# Power_Stage.net
KiCad netlist of a schematic drawn in Altium Designer
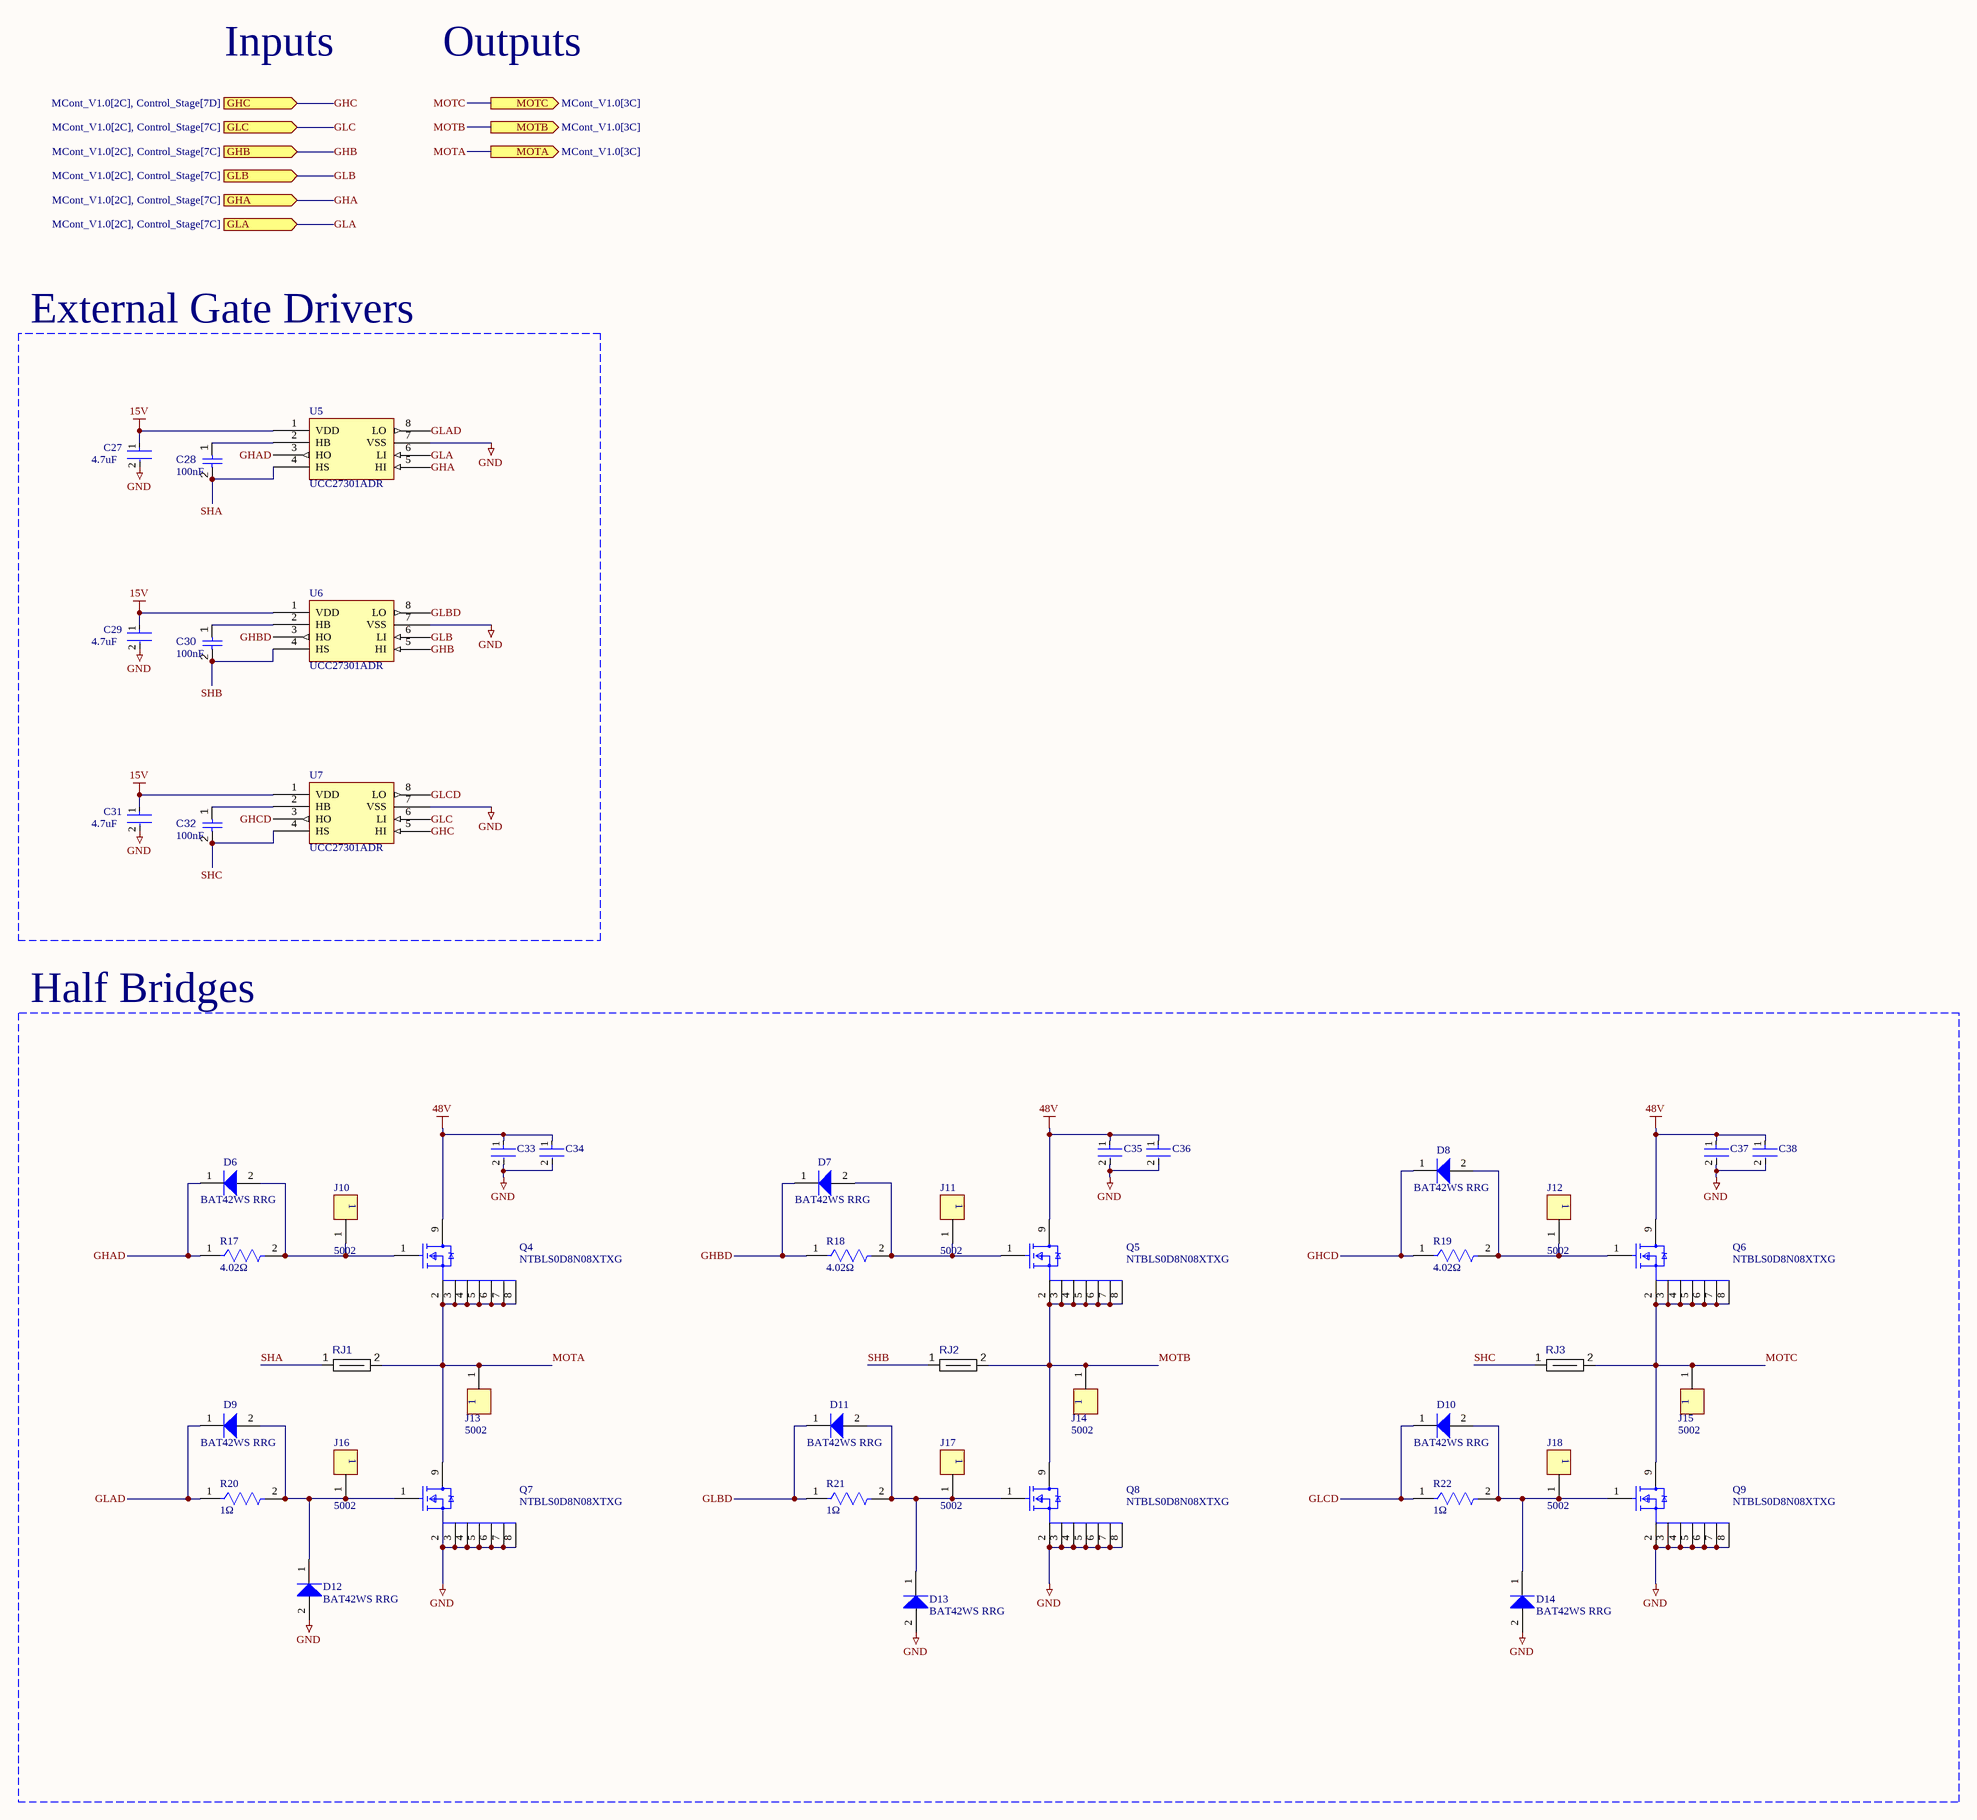
[diagram p0: Power_Stage.SchDoc]

(export (version "E")
  (design (tool "Eeschema 10.0.6"))
  (components
    (comp (ref "C27")
      (value "CL21A475KAQNNNE")
      (footprint "FP-CL21-IPC_A")
      (description "CL21 Series 0805 4.7uF 25V ±10% Tolerance X5R Multilayer Ceramic Chip Capacitor")
      (fields (field (name "CAPACITANCE") "4.7uF") (field (name "TOLERANCE") "10%"))
      (libsource (lib "Altium Content Vault") (part "b4654b650e69147ec39a6b967a45e02"))
    )
    (comp (ref "C28")
      (value "100nF")
      (footprint "FP-CL10-IPC_B")
      (fields (field (name "Comment") "CL10B104KC8NNNC"))
      (libsource (lib "CEV Electrical") (part "CAP-NP-2"))
    )
    (comp (ref "C29")
      (value "CL21A475KAQNNNE")
      (footprint "FP-CL21-IPC_A")
      (description "CL21 Series 0805 4.7uF 25V ±10% Tolerance X5R Multilayer Ceramic Chip Capacitor")
      (fields (field (name "CAPACITANCE") "4.7uF") (field (name "TOLERANCE") "10%"))
      (libsource (lib "Altium Content Vault") (part "b4654b650e69147ec39a6b967a45e02"))
    )
    (comp (ref "C30")
      (value "100nF")
      (footprint "FP-CL10-IPC_B")
      (fields (field (name "Comment") "CL10B104KC8NNNC"))
      (libsource (lib "CEV Electrical") (part "CAP-NP-2"))
    )
    (comp (ref "C31")
      (value "CL21A475KAQNNNE")
      (footprint "FP-CL21-IPC_A")
      (description "CL21 Series 0805 4.7uF 25V ±10% Tolerance X5R Multilayer Ceramic Chip Capacitor")
      (fields (field (name "CAPACITANCE") "4.7uF") (field (name "TOLERANCE") "10%"))
      (libsource (lib "Altium Content Vault") (part "b4654b650e69147ec39a6b967a45e02"))
    )
    (comp (ref "C32")
      (value "100nF")
      (footprint "FP-CL10-IPC_B")
      (fields (field (name "Comment") "CL10B104KC8NNNC"))
      (libsource (lib "CEV Electrical") (part "CAP-NP-2"))
    )
    (comp (ref "C33")
      (value "C1210C105K1RACTU")
      (footprint "FP-C1210C105K1RACTU-MFG")
      (description "CAP CER 1UF 100V X7R 1210")
      (fields (field (name "VOLTAGE") "100V") (field (name "TOLERANCE") "10%"))
      (libsource (lib "Altium Content Vault") (part "b4654b650e69147ec39a6b967a45e02"))
    )
    (comp (ref "C34")
      (value "C1210C105K1RACTU")
      (footprint "FP-C1210C105K1RACTU-MFG")
      (description "CAP CER 1UF 100V X7R 1210")
      (fields (field (name "VOLTAGE") "100V") (field (name "TOLERANCE") "10%"))
      (libsource (lib "Altium Content Vault") (part "b4654b650e69147ec39a6b967a45e02"))
    )
    (comp (ref "C35")
      (value "C1210C105K1RACTU")
      (footprint "FP-C1210C105K1RACTU-MFG")
      (description "CAP CER 1UF 100V X7R 1210")
      (fields (field (name "VOLTAGE") "100V") (field (name "TOLERANCE") "10%"))
      (libsource (lib "Altium Content Vault") (part "b4654b650e69147ec39a6b967a45e02"))
    )
    (comp (ref "C36")
      (value "C1210C105K1RACTU")
      (footprint "FP-C1210C105K1RACTU-MFG")
      (description "CAP CER 1UF 100V X7R 1210")
      (fields (field (name "VOLTAGE") "100V") (field (name "TOLERANCE") "10%"))
      (libsource (lib "Altium Content Vault") (part "b4654b650e69147ec39a6b967a45e02"))
    )
    (comp (ref "C37")
      (value "C1210C105K1RACTU")
      (footprint "FP-C1210C105K1RACTU-MFG")
      (description "CAP CER 1UF 100V X7R 1210")
      (fields (field (name "VOLTAGE") "100V") (field (name "TOLERANCE") "10%"))
      (libsource (lib "Altium Content Vault") (part "b4654b650e69147ec39a6b967a45e02"))
    )
    (comp (ref "C38")
      (value "C1210C105K1RACTU")
      (footprint "FP-C1210C105K1RACTU-MFG")
      (description "CAP CER 1UF 100V X7R 1210")
      (fields (field (name "VOLTAGE") "100V") (field (name "TOLERANCE") "10%"))
      (libsource (lib "Altium Content Vault") (part "b4654b650e69147ec39a6b967a45e02"))
    )
    (comp (ref "D6")
      (value "BAT42WS RRG")
      (footprint "BAT42WS RRG-Footprint-1")
      (description "Schottky Diode, 30V, 0.2A, Sod-323F Rohs Compliant: Yes")
      (libsource (lib "CEV Electrical New") (part "BAT42WS RRG-Symbol-1"))
    )
    (comp (ref "D7")
      (value "BAT42WS RRG")
      (footprint "BAT42WS RRG-Footprint-1")
      (description "Schottky Diode, 30V, 0.2A, Sod-323F Rohs Compliant: Yes")
      (libsource (lib "CEV Electrical New") (part "BAT42WS RRG-Symbol-1"))
    )
    (comp (ref "D8")
      (value "BAT42WS RRG")
      (footprint "BAT42WS RRG-Footprint-1")
      (description "Schottky Diode, 30V, 0.2A, Sod-323F Rohs Compliant: Yes")
      (libsource (lib "CEV Electrical New") (part "BAT42WS RRG-Symbol-1"))
    )
    (comp (ref "D9")
      (value "BAT42WS RRG")
      (footprint "BAT42WS RRG-Footprint-1")
      (description "Schottky Diode, 30V, 0.2A, Sod-323F Rohs Compliant: Yes")
      (libsource (lib "CEV Electrical New") (part "BAT42WS RRG-Symbol-1"))
    )
    (comp (ref "D10")
      (value "BAT42WS RRG")
      (footprint "BAT42WS RRG-Footprint-1")
      (description "Schottky Diode, 30V, 0.2A, Sod-323F Rohs Compliant: Yes")
      (libsource (lib "CEV Electrical New") (part "BAT42WS RRG-Symbol-1"))
    )
    (comp (ref "D11")
      (value "BAT42WS RRG")
      (footprint "BAT42WS RRG-Footprint-1")
      (description "Schottky Diode, 30V, 0.2A, Sod-323F Rohs Compliant: Yes")
      (libsource (lib "CEV Electrical New") (part "BAT42WS RRG-Symbol-1"))
    )
    (comp (ref "D12")
      (value "BAT42WS RRG")
      (footprint "BAT42WS RRG-Footprint-1")
      (description "Schottky Diode, 30V, 0.2A, Sod-323F Rohs Compliant: Yes")
      (libsource (lib "CEV Electrical New") (part "BAT42WS RRG-Symbol-1"))
    )
    (comp (ref "D13")
      (value "BAT42WS RRG")
      (footprint "BAT42WS RRG-Footprint-1")
      (description "Schottky Diode, 30V, 0.2A, Sod-323F Rohs Compliant: Yes")
      (libsource (lib "CEV Electrical New") (part "BAT42WS RRG-Symbol-1"))
    )
    (comp (ref "D14")
      (value "BAT42WS RRG")
      (footprint "BAT42WS RRG-Footprint-1")
      (description "Schottky Diode, 30V, 0.2A, Sod-323F Rohs Compliant: Yes")
      (libsource (lib "CEV Electrical New") (part "BAT42WS RRG-Symbol-1"))
    )
    (comp (ref "J10")
      (value "5002")
      (footprint "FP-5002-MFG")
      (description "PC TEST POINT MINIATURE WHITE")
      (libsource (lib "Altium Content Vault") (part "1e4615820a309e3ce90f9e6d957b7fa"))
    )
    (comp (ref "J11")
      (value "5002")
      (footprint "FP-5002-MFG")
      (description "PC TEST POINT MINIATURE WHITE")
      (libsource (lib "Altium Content Vault") (part "1e4615820a309e3ce90f9e6d957b7fa"))
    )
    (comp (ref "J12")
      (value "5002")
      (footprint "FP-5002-MFG")
      (description "PC TEST POINT MINIATURE WHITE")
      (libsource (lib "Altium Content Vault") (part "1e4615820a309e3ce90f9e6d957b7fa"))
    )
    (comp (ref "J13")
      (value "5002")
      (footprint "FP-5002-MFG")
      (description "PC TEST POINT MINIATURE WHITE")
      (libsource (lib "") (part "1e4615820a309e3ce90f9e6d957b7fa_1"))
    )
    (comp (ref "J14")
      (value "5002")
      (footprint "FP-5002-MFG")
      (description "PC TEST POINT MINIATURE WHITE")
      (libsource (lib "") (part "1e4615820a309e3ce90f9e6d957b7fa_1"))
    )
    (comp (ref "J15")
      (value "5002")
      (footprint "FP-5002-MFG")
      (description "PC TEST POINT MINIATURE WHITE")
      (libsource (lib "") (part "1e4615820a309e3ce90f9e6d957b7fa_1"))
    )
    (comp (ref "J16")
      (value "5002")
      (footprint "FP-5002-MFG")
      (description "PC TEST POINT MINIATURE WHITE")
      (libsource (lib "Altium Content Vault") (part "1e4615820a309e3ce90f9e6d957b7fa"))
    )
    (comp (ref "J17")
      (value "5002")
      (footprint "FP-5002-MFG")
      (description "PC TEST POINT MINIATURE WHITE")
      (libsource (lib "Altium Content Vault") (part "1e4615820a309e3ce90f9e6d957b7fa"))
    )
    (comp (ref "J18")
      (value "5002")
      (footprint "FP-5002-MFG")
      (description "PC TEST POINT MINIATURE WHITE")
      (libsource (lib "Altium Content Vault") (part "1e4615820a309e3ce90f9e6d957b7fa"))
    )
    (comp (ref "Q4")
      (value "NTBLS0D8N08XTXG")
      (footprint "NTBLS0D8N08XTXG")
      (description "NTBL Series N-Channel 457A 325W Surface Mount Power Mosfet HPSOF-8")
      (libsource (lib "CEV Electrical New") (part "NTBLS0D8N08XTXG"))
    )
    (comp (ref "Q5")
      (value "NTBLS0D8N08XTXG")
      (footprint "NTBLS0D8N08XTXG")
      (description "NTBL Series N-Channel 457A 325W Surface Mount Power Mosfet HPSOF-8")
      (libsource (lib "CEV Electrical New") (part "NTBLS0D8N08XTXG"))
    )
    (comp (ref "Q6")
      (value "NTBLS0D8N08XTXG")
      (footprint "NTBLS0D8N08XTXG")
      (description "NTBL Series N-Channel 457A 325W Surface Mount Power Mosfet HPSOF-8")
      (libsource (lib "CEV Electrical New") (part "NTBLS0D8N08XTXG"))
    )
    (comp (ref "Q7")
      (value "NTBLS0D8N08XTXG")
      (footprint "NTBLS0D8N08XTXG")
      (description "NTBL Series N-Channel 457A 325W Surface Mount Power Mosfet HPSOF-8")
      (libsource (lib "CEV Electrical New") (part "NTBLS0D8N08XTXG"))
    )
    (comp (ref "Q8")
      (value "NTBLS0D8N08XTXG")
      (footprint "NTBLS0D8N08XTXG")
      (description "NTBL Series N-Channel 457A 325W Surface Mount Power Mosfet HPSOF-8")
      (libsource (lib "CEV Electrical New") (part "NTBLS0D8N08XTXG"))
    )
    (comp (ref "Q9")
      (value "NTBLS0D8N08XTXG")
      (footprint "NTBLS0D8N08XTXG")
      (description "NTBL Series N-Channel 457A 325W Surface Mount Power Mosfet HPSOF-8")
      (libsource (lib "CEV Electrical New") (part "NTBLS0D8N08XTXG"))
    )
    (comp (ref "R17")
      (value "4.02Ω")
      (footprint "CRCW06034R02FKEAHP-Footprint-1")
      (description "Res Thick Film 0603 4.02 Ohm 1% 0.33W(1/3W) ±100ppm/C Pad SMD Automotive T/R")
      (fields (field (name "TOLERANCE") "1%") (field (name "Comment") "CRCW06034R02FKEAHP"))
      (libsource (lib "CEV Electrical New") (part "CRCW06034R02FKEAHP-Symbol-1"))
    )
    (comp (ref "R18")
      (value "4.02Ω")
      (footprint "CRCW06034R02FKEAHP-Footprint-1")
      (description "Res Thick Film 0603 4.02 Ohm 1% 0.33W(1/3W) ±100ppm/C Pad SMD Automotive T/R")
      (fields (field (name "TOLERANCE") "1%") (field (name "Comment") "CRCW06034R02FKEAHP"))
      (libsource (lib "CEV Electrical New") (part "CRCW06034R02FKEAHP-Symbol-1"))
    )
    (comp (ref "R19")
      (value "4.02Ω")
      (footprint "CRCW06034R02FKEAHP-Footprint-1")
      (description "Res Thick Film 0603 4.02 Ohm 1% 0.33W(1/3W) ±100ppm/C Pad SMD Automotive T/R")
      (fields (field (name "TOLERANCE") "1%") (field (name "Comment") "CRCW06034R02FKEAHP"))
      (libsource (lib "CEV Electrical New") (part "CRCW06034R02FKEAHP-Symbol-1"))
    )
    (comp (ref "R20")
      (value "1Ω")
      (footprint "SR0603FR-7T1RL-Footprint-1")
      (description "Res Thick Film 0603 1 Ohm 1% 0.25W(1/4W) ±200ppm/C Pad SMD Automotive T/R")
      (fields (field (name "TOLERANCE") "1%") (field (name "Comment") "SR0603FR-7T1RL"))
      (libsource (lib "CEV Electrical New") (part "SR0603FR-7T1RL-Symbol-1"))
    )
    (comp (ref "R21")
      (value "1Ω")
      (footprint "SR0603FR-7T1RL-Footprint-1")
      (description "Res Thick Film 0603 1 Ohm 1% 0.25W(1/4W) ±200ppm/C Pad SMD Automotive T/R")
      (fields (field (name "TOLERANCE") "1%") (field (name "Comment") "SR0603FR-7T1RL"))
      (libsource (lib "CEV Electrical New") (part "SR0603FR-7T1RL-Symbol-1"))
    )
    (comp (ref "R22")
      (value "1Ω")
      (footprint "SR0603FR-7T1RL-Footprint-1")
      (description "Res Thick Film 0603 1 Ohm 1% 0.25W(1/4W) ±200ppm/C Pad SMD Automotive T/R")
      (fields (field (name "TOLERANCE") "1%") (field (name "Comment") "SR0603FR-7T1RL"))
      (libsource (lib "CEV Electrical New") (part "SR0603FR-7T1RL-Symbol-1"))
    )
    (comp (ref "RJ1")
      (value "Net Tie 30x70mil")
      (footprint "Net Tie 10x20mil-Footprint-1")
      (libsource (lib "CEV Electrical") (part "Net Tie"))
    )
    (comp (ref "RJ2")
      (value "Net Tie 30x70mil")
      (footprint "Net Tie 10x20mil-Footprint-1")
      (libsource (lib "CEV Electrical") (part "Net Tie"))
    )
    (comp (ref "RJ3")
      (value "Net Tie 30x70mil")
      (footprint "Net Tie 10x20mil-Footprint-1")
      (libsource (lib "CEV Electrical") (part "Net Tie"))
    )
    (comp (ref "U5")
      (value "UCC27301ADR")
      (footprint "SOIC127P600X175-8N")
      (description "120V 4.5A half-bridge driver with 8V UVLO, interlock, and enable options 8-SOIC -40 to 150")
      (libsource (lib "CEV Electrical New") (part "UCC27301ADR-Symbol-1"))
    )
    (comp (ref "U6")
      (value "UCC27301ADR")
      (footprint "SOIC127P600X175-8N")
      (description "120V 4.5A half-bridge driver with 8V UVLO, interlock, and enable options 8-SOIC -40 to 150")
      (libsource (lib "CEV Electrical New") (part "UCC27301ADR-Symbol-1"))
    )
    (comp (ref "U7")
      (value "UCC27301ADR")
      (footprint "SOIC127P600X175-8N")
      (description "120V 4.5A half-bridge driver with 8V UVLO, interlock, and enable options 8-SOIC -40 to 150")
      (libsource (lib "CEV Electrical New") (part "UCC27301ADR-Symbol-1"))
    )
  )
  (nets
    (net (code "1") (name "/GHA") (class "Default")
      (node (ref "U5") (pin "5") (pinfunction "HI_5") (pintype "input"))
    )
    (net (code "2") (name "/GHAD") (class "Default")
      (node (ref "D6") (pin "1") (pinfunction "K_1") (pintype "passive"))
      (node (ref "R17") (pin "1") (pinfunction "1_1") (pintype "passive"))
      (node (ref "U5") (pin "3") (pinfunction "HO_3") (pintype "output"))
    )
    (net (code "3") (name "/GHB") (class "Default")
      (node (ref "U6") (pin "5") (pinfunction "HI_5") (pintype "input"))
    )
    (net (code "4") (name "/GHBD") (class "Default")
      (node (ref "D7") (pin "1") (pinfunction "K_1") (pintype "passive"))
      (node (ref "R18") (pin "1") (pinfunction "1_1") (pintype "passive"))
      (node (ref "U6") (pin "3") (pinfunction "HO_3") (pintype "output"))
    )
    (net (code "5") (name "/GHC") (class "Default")
      (node (ref "U7") (pin "5") (pinfunction "HI_5") (pintype "input"))
    )
    (net (code "6") (name "/GHCD") (class "Default")
      (node (ref "D8") (pin "1") (pinfunction "K_1") (pintype "passive"))
      (node (ref "R19") (pin "1") (pinfunction "1_1") (pintype "passive"))
      (node (ref "U7") (pin "3") (pinfunction "HO_3") (pintype "output"))
    )
    (net (code "7") (name "/GLA") (class "Default")
      (node (ref "U5") (pin "6") (pinfunction "LI_6") (pintype "input"))
    )
    (net (code "8") (name "/GLAD") (class "Default")
      (node (ref "D9") (pin "1") (pinfunction "K_1") (pintype "passive"))
      (node (ref "R20") (pin "1") (pinfunction "1_1") (pintype "passive"))
      (node (ref "U5") (pin "8") (pinfunction "LO_8") (pintype "output"))
    )
    (net (code "9") (name "/GLB") (class "Default")
      (node (ref "U6") (pin "6") (pinfunction "LI_6") (pintype "input"))
    )
    (net (code "10") (name "/GLBD") (class "Default")
      (node (ref "D11") (pin "1") (pinfunction "K_1") (pintype "passive"))
      (node (ref "R21") (pin "1") (pinfunction "1_1") (pintype "passive"))
      (node (ref "U6") (pin "8") (pinfunction "LO_8") (pintype "output"))
    )
    (net (code "11") (name "/GLC") (class "Default")
      (node (ref "U7") (pin "6") (pinfunction "LI_6") (pintype "input"))
    )
    (net (code "12") (name "/GLCD") (class "Default")
      (node (ref "D10") (pin "1") (pinfunction "K_1") (pintype "passive"))
      (node (ref "R22") (pin "1") (pinfunction "1_1") (pintype "passive"))
      (node (ref "U7") (pin "8") (pinfunction "LO_8") (pintype "output"))
    )
    (net (code "13") (name "/MOTA") (class "Default")
      (node (ref "J13") (pin "1") (pinfunction "1_1") (pintype "passive"))
      (node (ref "Q4") (pin "2") (pinfunction "Source_2") (pintype "passive"))
      (node (ref "Q4") (pin "3") (pinfunction "Source_3") (pintype "passive"))
      (node (ref "Q4") (pin "4") (pinfunction "Source_4") (pintype "passive"))
      (node (ref "Q4") (pin "5") (pinfunction "Source_5") (pintype "passive"))
      (node (ref "Q4") (pin "6") (pinfunction "Source_6") (pintype "passive"))
      (node (ref "Q4") (pin "7") (pinfunction "Source_7") (pintype "passive"))
      (node (ref "Q4") (pin "8") (pinfunction "Source_8") (pintype "passive"))
      (node (ref "Q7") (pin "9") (pinfunction "Drain_9") (pintype "passive"))
      (node (ref "RJ1") (pin "2") (pinfunction "2_2") (pintype "passive"))
    )
    (net (code "14") (name "/MOTB") (class "Default")
      (node (ref "J14") (pin "1") (pinfunction "1_1") (pintype "passive"))
      (node (ref "Q5") (pin "2") (pinfunction "Source_2") (pintype "passive"))
      (node (ref "Q5") (pin "3") (pinfunction "Source_3") (pintype "passive"))
      (node (ref "Q5") (pin "4") (pinfunction "Source_4") (pintype "passive"))
      (node (ref "Q5") (pin "5") (pinfunction "Source_5") (pintype "passive"))
      (node (ref "Q5") (pin "6") (pinfunction "Source_6") (pintype "passive"))
      (node (ref "Q5") (pin "7") (pinfunction "Source_7") (pintype "passive"))
      (node (ref "Q5") (pin "8") (pinfunction "Source_8") (pintype "passive"))
      (node (ref "Q8") (pin "9") (pinfunction "Drain_9") (pintype "passive"))
      (node (ref "RJ2") (pin "2") (pinfunction "2_2") (pintype "passive"))
    )
    (net (code "15") (name "/MOTC") (class "Default")
      (node (ref "J15") (pin "1") (pinfunction "1_1") (pintype "passive"))
      (node (ref "Q6") (pin "2") (pinfunction "Source_2") (pintype "passive"))
      (node (ref "Q6") (pin "3") (pinfunction "Source_3") (pintype "passive"))
      (node (ref "Q6") (pin "4") (pinfunction "Source_4") (pintype "passive"))
      (node (ref "Q6") (pin "5") (pinfunction "Source_5") (pintype "passive"))
      (node (ref "Q6") (pin "6") (pinfunction "Source_6") (pintype "passive"))
      (node (ref "Q6") (pin "7") (pinfunction "Source_7") (pintype "passive"))
      (node (ref "Q6") (pin "8") (pinfunction "Source_8") (pintype "passive"))
      (node (ref "Q9") (pin "9") (pinfunction "Drain_9") (pintype "passive"))
      (node (ref "RJ3") (pin "2") (pinfunction "2_2") (pintype "passive"))
    )
    (net (code "16") (name "/SHA") (class "Default")
      (node (ref "C28") (pin "2") (pinfunction "2_2") (pintype "passive"))
      (node (ref "RJ1") (pin "1") (pinfunction "1_1") (pintype "passive"))
      (node (ref "U5") (pin "4") (pinfunction "HS_4") (pintype "passive"))
    )
    (net (code "17") (name "/SHB") (class "Default")
      (node (ref "C30") (pin "2") (pinfunction "2_2") (pintype "passive"))
      (node (ref "RJ2") (pin "1") (pinfunction "1_1") (pintype "passive"))
      (node (ref "U6") (pin "4") (pinfunction "HS_4") (pintype "passive"))
    )
    (net (code "18") (name "/SHC") (class "Default")
      (node (ref "C32") (pin "2") (pinfunction "2_2") (pintype "passive"))
      (node (ref "RJ3") (pin "1") (pinfunction "1_1") (pintype "passive"))
      (node (ref "U7") (pin "4") (pinfunction "HS_4") (pintype "passive"))
    )
    (net (code "19") (name "15V") (class "Default")
      (node (ref "C27") (pin "1") (pinfunction "1_1") (pintype "passive"))
      (node (ref "C29") (pin "1") (pinfunction "1_1") (pintype "passive"))
      (node (ref "C31") (pin "1") (pinfunction "1_1") (pintype "passive"))
      (node (ref "U5") (pin "1") (pinfunction "VDD_1") (pintype "power_in"))
      (node (ref "U6") (pin "1") (pinfunction "VDD_1") (pintype "power_in"))
      (node (ref "U7") (pin "1") (pinfunction "VDD_1") (pintype "power_in"))
    )
    (net (code "20") (name "48V") (class "Default")
      (node (ref "C33") (pin "1") (pinfunction "1_1") (pintype "passive"))
      (node (ref "C34") (pin "1") (pinfunction "1_1") (pintype "passive"))
      (node (ref "C35") (pin "1") (pinfunction "1_1") (pintype "passive"))
      (node (ref "C36") (pin "1") (pinfunction "1_1") (pintype "passive"))
      (node (ref "C37") (pin "1") (pinfunction "1_1") (pintype "passive"))
      (node (ref "C38") (pin "1") (pinfunction "1_1") (pintype "passive"))
      (node (ref "Q4") (pin "9") (pinfunction "Drain_9") (pintype "passive"))
      (node (ref "Q5") (pin "9") (pinfunction "Drain_9") (pintype "passive"))
      (node (ref "Q6") (pin "9") (pinfunction "Drain_9") (pintype "passive"))
    )
    (net (code "21") (name "GND") (class "Default")
      (node (ref "C27") (pin "2") (pinfunction "2_2") (pintype "passive"))
      (node (ref "C29") (pin "2") (pinfunction "2_2") (pintype "passive"))
      (node (ref "C31") (pin "2") (pinfunction "2_2") (pintype "passive"))
      (node (ref "C33") (pin "2") (pinfunction "2_2") (pintype "passive"))
      (node (ref "C34") (pin "2") (pinfunction "2_2") (pintype "passive"))
      (node (ref "C35") (pin "2") (pinfunction "2_2") (pintype "passive"))
      (node (ref "C36") (pin "2") (pinfunction "2_2") (pintype "passive"))
      (node (ref "C37") (pin "2") (pinfunction "2_2") (pintype "passive"))
      (node (ref "C38") (pin "2") (pinfunction "2_2") (pintype "passive"))
      (node (ref "D12") (pin "2") (pinfunction "A_2") (pintype "passive"))
      (node (ref "D13") (pin "2") (pinfunction "A_2") (pintype "passive"))
      (node (ref "D14") (pin "2") (pinfunction "A_2") (pintype "passive"))
      (node (ref "Q7") (pin "2") (pinfunction "Source_2") (pintype "passive"))
      (node (ref "Q7") (pin "3") (pinfunction "Source_3") (pintype "passive"))
      (node (ref "Q7") (pin "4") (pinfunction "Source_4") (pintype "passive"))
      (node (ref "Q7") (pin "5") (pinfunction "Source_5") (pintype "passive"))
      (node (ref "Q7") (pin "6") (pinfunction "Source_6") (pintype "passive"))
      (node (ref "Q7") (pin "7") (pinfunction "Source_7") (pintype "passive"))
      (node (ref "Q7") (pin "8") (pinfunction "Source_8") (pintype "passive"))
      (node (ref "Q8") (pin "2") (pinfunction "Source_2") (pintype "passive"))
      (node (ref "Q8") (pin "3") (pinfunction "Source_3") (pintype "passive"))
      (node (ref "Q8") (pin "4") (pinfunction "Source_4") (pintype "passive"))
      (node (ref "Q8") (pin "5") (pinfunction "Source_5") (pintype "passive"))
      (node (ref "Q8") (pin "6") (pinfunction "Source_6") (pintype "passive"))
      (node (ref "Q8") (pin "7") (pinfunction "Source_7") (pintype "passive"))
      (node (ref "Q8") (pin "8") (pinfunction "Source_8") (pintype "passive"))
      (node (ref "Q9") (pin "2") (pinfunction "Source_2") (pintype "passive"))
      (node (ref "Q9") (pin "3") (pinfunction "Source_3") (pintype "passive"))
      (node (ref "Q9") (pin "4") (pinfunction "Source_4") (pintype "passive"))
      (node (ref "Q9") (pin "5") (pinfunction "Source_5") (pintype "passive"))
      (node (ref "Q9") (pin "6") (pinfunction "Source_6") (pintype "passive"))
      (node (ref "Q9") (pin "7") (pinfunction "Source_7") (pintype "passive"))
      (node (ref "Q9") (pin "8") (pinfunction "Source_8") (pintype "passive"))
      (node (ref "U5") (pin "7") (pinfunction "VSS_7") (pintype "power_in"))
      (node (ref "U6") (pin "7") (pinfunction "VSS_7") (pintype "power_in"))
      (node (ref "U7") (pin "7") (pinfunction "VSS_7") (pintype "power_in"))
    )
    (net (code "22") (name "Net-(D6-A)") (class "Default")
      (node (ref "D6") (pin "2") (pinfunction "A_2") (pintype "passive"))
      (node (ref "J10") (pin "1") (pinfunction "1_1") (pintype "passive"))
      (node (ref "Q4") (pin "1") (pinfunction "Gate_1") (pintype "passive"))
      (node (ref "R17") (pin "2") (pinfunction "2_2") (pintype "passive"))
    )
    (net (code "23") (name "Net-(D7-A)") (class "Default")
      (node (ref "D7") (pin "2") (pinfunction "A_2") (pintype "passive"))
      (node (ref "J11") (pin "1") (pinfunction "1_1") (pintype "passive"))
      (node (ref "Q5") (pin "1") (pinfunction "Gate_1") (pintype "passive"))
      (node (ref "R18") (pin "2") (pinfunction "2_2") (pintype "passive"))
    )
    (net (code "24") (name "Net-(D8-A)") (class "Default")
      (node (ref "D8") (pin "2") (pinfunction "A_2") (pintype "passive"))
      (node (ref "J12") (pin "1") (pinfunction "1_1") (pintype "passive"))
      (node (ref "Q6") (pin "1") (pinfunction "Gate_1") (pintype "passive"))
      (node (ref "R19") (pin "2") (pinfunction "2_2") (pintype "passive"))
    )
    (net (code "25") (name "Net-(D10-A)") (class "Default")
      (node (ref "D10") (pin "2") (pinfunction "A_2") (pintype "passive"))
      (node (ref "D14") (pin "1") (pinfunction "K_1") (pintype "passive"))
      (node (ref "J18") (pin "1") (pinfunction "1_1") (pintype "passive"))
      (node (ref "Q9") (pin "1") (pinfunction "Gate_1") (pintype "passive"))
      (node (ref "R22") (pin "2") (pinfunction "2_2") (pintype "passive"))
    )
    (net (code "26") (name "Net-(D11-A)") (class "Default")
      (node (ref "D11") (pin "2") (pinfunction "A_2") (pintype "passive"))
      (node (ref "D13") (pin "1") (pinfunction "K_1") (pintype "passive"))
      (node (ref "J17") (pin "1") (pinfunction "1_1") (pintype "passive"))
      (node (ref "Q8") (pin "1") (pinfunction "Gate_1") (pintype "passive"))
      (node (ref "R21") (pin "2") (pinfunction "2_2") (pintype "passive"))
    )
    (net (code "27") (name "Net-(D12-K)") (class "Default")
      (node (ref "D12") (pin "1") (pinfunction "K_1") (pintype "passive"))
      (node (ref "D9") (pin "2") (pinfunction "A_2") (pintype "passive"))
      (node (ref "J16") (pin "1") (pinfunction "1_1") (pintype "passive"))
      (node (ref "Q7") (pin "1") (pinfunction "Gate_1") (pintype "passive"))
      (node (ref "R20") (pin "2") (pinfunction "2_2") (pintype "passive"))
    )
    (net (code "28") (name "Net-(U5-HB)") (class "Default")
      (node (ref "C28") (pin "1") (pinfunction "1_1") (pintype "passive"))
      (node (ref "U5") (pin "2") (pinfunction "HB_2") (pintype "passive"))
    )
    (net (code "29") (name "Net-(U6-HB)") (class "Default")
      (node (ref "C30") (pin "1") (pinfunction "1_1") (pintype "passive"))
      (node (ref "U6") (pin "2") (pinfunction "HB_2") (pintype "passive"))
    )
    (net (code "30") (name "Net-(U7-HB)") (class "Default")
      (node (ref "C32") (pin "1") (pinfunction "1_1") (pintype "passive"))
      (node (ref "U7") (pin "2") (pinfunction "HB_2") (pintype "passive"))
    )
  )
)
